# Store.net
KiCad netlist of a schematic drawn in Altium Designer
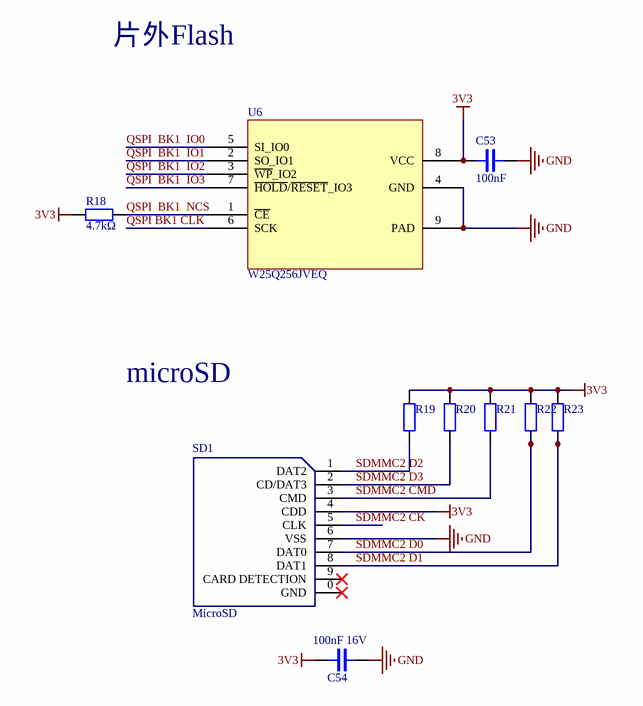
[diagram p0: Store.SchDoc]

(export (version "E")
  (design (tool "Eeschema 10.0.6"))
  (components
    (comp (ref "C53")
      (value "100nF")
      (footprint "0805")
      (description "Capacitor")
      (libsource (lib "General") (part "CAP"))
    )
    (comp (ref "C54")
      (value "100nF 16V")
      (footprint "CAP-1812")
      (description "Capacitor")
      (libsource (lib "General") (part "CAP"))
    )
    (comp (ref "R18")
      (value "4.7kΩ")
      (footprint "0805")
      (description "Resistor")
      (libsource (lib "") (part "RES_1"))
    )
    (comp (ref "R19")
      (value "10kΩ")
      (footprint "0805")
      (description "Resistor")
      (libsource (lib "General") (part "RES"))
    )
    (comp (ref "R20")
      (value "10kΩ")
      (footprint "0805")
      (description "Resistor")
      (libsource (lib "General") (part "RES"))
    )
    (comp (ref "R21")
      (value "10kΩ")
      (footprint "0805")
      (description "Resistor")
      (libsource (lib "General") (part "RES"))
    )
    (comp (ref "R22")
      (value "10kΩ")
      (footprint "0805")
      (description "Resistor")
      (libsource (lib "General") (part "RES"))
    )
    (comp (ref "R23")
      (value "10kΩ")
      (footprint "0805")
      (description "Resistor")
      (libsource (lib "General") (part "RES"))
    )
    (comp (ref "SD1") (value "MicroSD") (footprint "Micro SD") (libsource (lib "SD Card") (part "MicroSD")))
    (comp (ref "U6") (value "W25Q256JVEQ") (libsource (lib "MainBoard") (part "W25Q256JVEQ")))
  )
  (nets
    (net (code "1") (name "/QSPI  BK1  IO0") (class "Default")
      (node (ref "U6") (pin "5") (pinfunction "SI_IO0_5") (pintype "passive"))
    )
    (net (code "2") (name "/QSPI  BK1  IO1") (class "Default")
      (node (ref "U6") (pin "2") (pinfunction "SO_IO1_2") (pintype "passive"))
    )
    (net (code "3") (name "/QSPI  BK1  IO2") (class "Default")
      (node (ref "U6") (pin "3") (pinfunction "~{WP}_IO2_3") (pintype "passive"))
    )
    (net (code "4") (name "/QSPI  BK1  IO3") (class "Default")
      (node (ref "U6") (pin "7") (pinfunction "~{HOLD}/~{RESET}_IO3_7") (pintype "passive"))
    )
    (net (code "5") (name "/QSPI  BK1  NCS") (class "Default")
      (node (ref "R18") (pin "2") (pinfunction "2_2") (pintype "passive"))
      (node (ref "U6") (pin "1") (pinfunction "~{CE}_1") (pintype "passive"))
    )
    (net (code "6") (name "/QSPI BK1 CLK") (class "Default")
      (node (ref "U6") (pin "6") (pinfunction "SCK_6") (pintype "passive"))
    )
    (net (code "7") (name "/SDMMC2 CK") (class "Default")
      (node (ref "SD1") (pin "5") (pinfunction "CLK_5") (pintype "passive"))
    )
    (net (code "8") (name "/SDMMC2 CMD") (class "Default")
      (node (ref "R21") (pin "1") (pinfunction "1_1") (pintype "passive"))
      (node (ref "SD1") (pin "3") (pinfunction "CMD_3") (pintype "passive"))
    )
    (net (code "9") (name "/SDMMC2 D0") (class "Default")
      (node (ref "R22") (pin "1") (pinfunction "1_1") (pintype "passive"))
      (node (ref "SD1") (pin "7") (pinfunction "DAT0_7") (pintype "passive"))
    )
    (net (code "10") (name "/SDMMC2 D1") (class "Default")
      (node (ref "R23") (pin "1") (pinfunction "1_1") (pintype "passive"))
      (node (ref "SD1") (pin "8") (pinfunction "DAT1_8") (pintype "passive"))
    )
    (net (code "11") (name "/SDMMC2 D2") (class "Default")
      (node (ref "R19") (pin "1") (pinfunction "1_1") (pintype "passive"))
      (node (ref "SD1") (pin "1") (pinfunction "DAT2_1") (pintype "passive"))
    )
    (net (code "12") (name "/SDMMC2 D3") (class "Default")
      (node (ref "R20") (pin "1") (pinfunction "1_1") (pintype "passive"))
      (node (ref "SD1") (pin "2") (pinfunction "CD/DAT3_2") (pintype "passive"))
    )
    (net (code "13") (name "3V3") (class "Default")
      (node (ref "C53") (pin "1") (pinfunction "1_1") (pintype "passive"))
      (node (ref "C54") (pin "2") (pinfunction "2_2") (pintype "passive"))
      (node (ref "R18") (pin "1") (pinfunction "1_1") (pintype "passive"))
      (node (ref "R19") (pin "2") (pinfunction "2_2") (pintype "passive"))
      (node (ref "R20") (pin "2") (pinfunction "2_2") (pintype "passive"))
      (node (ref "R21") (pin "2") (pinfunction "2_2") (pintype "passive"))
      (node (ref "R22") (pin "2") (pinfunction "2_2") (pintype "passive"))
      (node (ref "R23") (pin "2") (pinfunction "2_2") (pintype "passive"))
      (node (ref "SD1") (pin "4") (pinfunction "CDD_4") (pintype "passive"))
      (node (ref "U6") (pin "8") (pinfunction "VCC_8") (pintype "passive"))
    )
    (net (code "14") (name "GND") (class "Default")
      (node (ref "C53") (pin "2") (pinfunction "2_2") (pintype "passive"))
      (node (ref "C54") (pin "1") (pinfunction "1_1") (pintype "passive"))
      (node (ref "SD1") (pin "6") (pinfunction "VSS_6") (pintype "passive"))
      (node (ref "U6") (pin "4") (pinfunction "GND_4") (pintype "passive"))
      (node (ref "U6") (pin "9") (pinfunction "PAD_9") (pintype "passive"))
    )
    (net (code "15") (name "unconnected-(SD1-CARD_DETECTION-Pad9)") (class "Default")
      (node (ref "SD1") (pin "9") (pinfunction "CARD_DETECTION_9") (pintype "passive+no_connect"))
    )
    (net (code "16") (name "unconnected-(SD1-GND-Pad0)") (class "Default")
      (node (ref "SD1") (pin "0") (pinfunction "GND_0") (pintype "passive+no_connect"))
    )
  )
)
